# 1.net
KiCad netlist of a schematic drawn in EAGLE
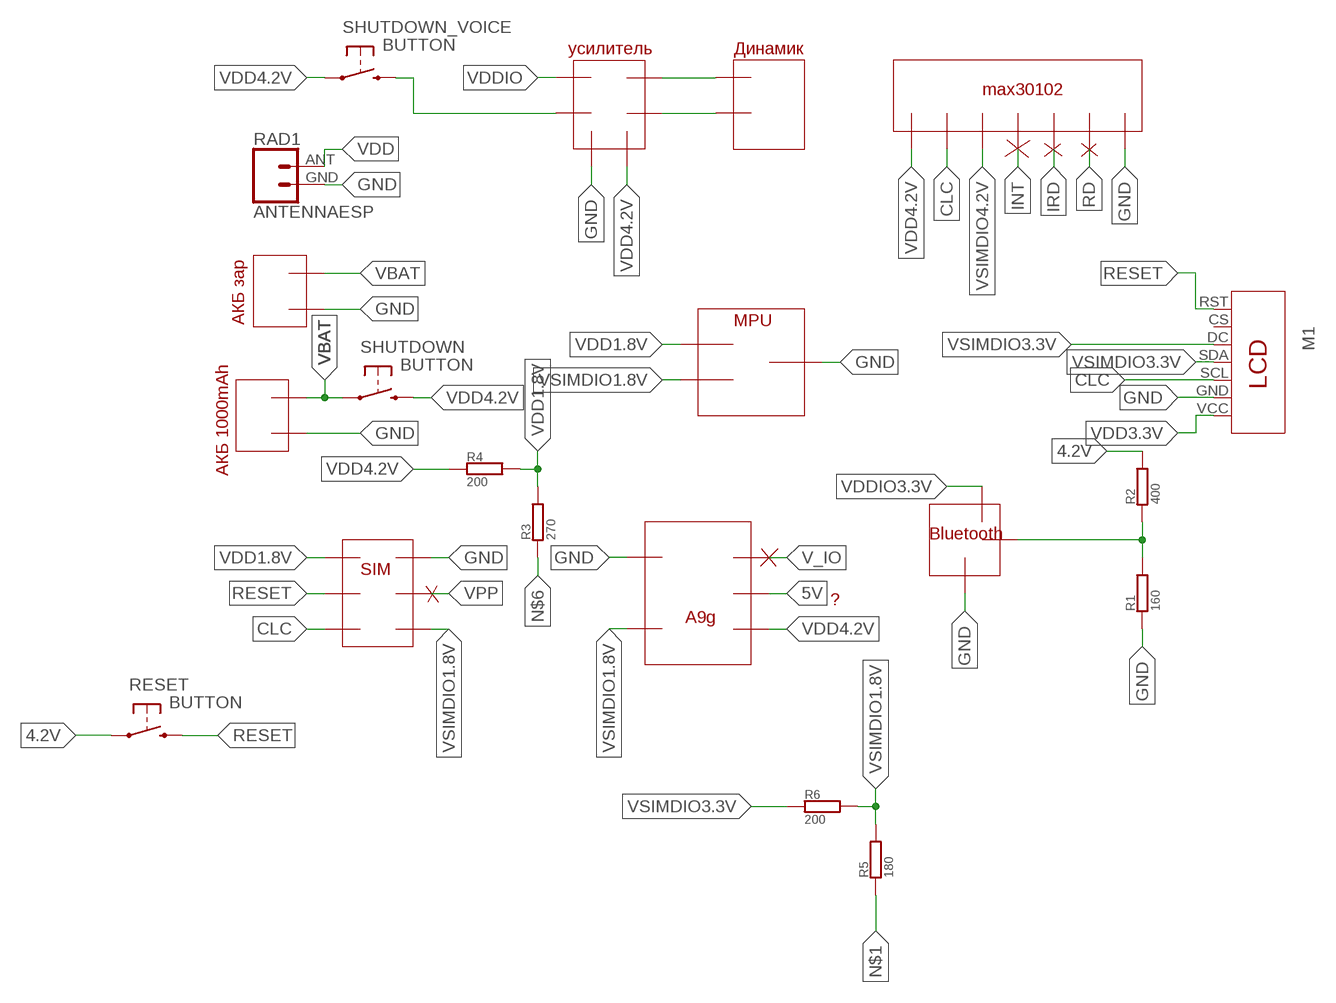
[diagram p0: schematic, sheet 1]

(export (version "E")
  (design (tool "Eeschema 10.0.6"))
  (components
    (comp (ref "M1")
      (value "1.28TFT")
      (footprint "eagle-import:TFT1.28INCH")
      (libsource (lib "eagle-import") (part "1.28TFT"))
    )
    (comp (ref "R1")
      (value "160")
      (footprint "eagle-import:0603")
      (libsource (lib "eagle-import") (part "R0603"))
    )
    (comp (ref "R2")
      (value "400")
      (footprint "eagle-import:0603")
      (libsource (lib "eagle-import") (part "R0603"))
    )
    (comp (ref "R3")
      (value "270")
      (footprint "eagle-import:0603")
      (libsource (lib "eagle-import") (part "R0603"))
    )
    (comp (ref "R4")
      (value "200")
      (footprint "eagle-import:0603")
      (libsource (lib "eagle-import") (part "R0603"))
    )
    (comp (ref "R5")
      (value "180")
      (footprint "eagle-import:0603")
      (libsource (lib "eagle-import") (part "R0603"))
    )
    (comp (ref "R6")
      (value "200")
      (footprint "eagle-import:0603")
      (libsource (lib "eagle-import") (part "R0603"))
    )
    (comp (ref "RAD1")
      (value "ANTENNAESP")
      (footprint "eagle-import:2.4GHZ")
      (libsource (lib "eagle-import") (part "ANTENNAESP"))
    )
    (comp (ref "RESET")
      (value "BUTTON")
      (footprint "eagle-import:BUTTON")
      (libsource (lib "eagle-import") (part "BUTTON"))
    )
    (comp (ref "SHUTDOWN")
      (value "BUTTON")
      (footprint "eagle-import:BUTTON")
      (libsource (lib "eagle-import") (part "BUTTON"))
    )
    (comp (ref "SHUTDOWN_VOICE")
      (value "BUTTON")
      (footprint "eagle-import:BUTTON")
      (libsource (lib "eagle-import") (part "BUTTON"))
    )
  )
  (nets
    (net (code "1") (name "4.2V") (class "Default")
      (node (ref "R2") (pin "P$2") (pinfunction "P$2_P$2") (pintype "bidirectional"))
      (node (ref "RESET") (pin "1") (pinfunction "3_1") (pintype "passive"))
    )
    (net (code "3") (name "CLC") (class "Default")
      (node (ref "M1") (pin "SCL") (pinfunction "P$5_SCL") (pintype "bidirectional"))
    )
    (net (code "4") (name "GND") (class "Default")
      (node (ref "M1") (pin "GND") (pinfunction "P$6_GND") (pintype "bidirectional"))
      (node (ref "R1") (pin "P$1") (pinfunction "P$1_P$1") (pintype "bidirectional"))
      (node (ref "RAD1") (pin "GND") (pinfunction "GND_GND") (pintype "passive"))
    )
    (net (code "7") (name "N$1") (class "Default")
      (node (ref "R5") (pin "P$1") (pinfunction "P$1_P$1") (pintype "bidirectional"))
    )
    (net (code "8") (name "N$6") (class "Default")
      (node (ref "R3") (pin "P$1") (pinfunction "P$1_P$1") (pintype "bidirectional"))
    )
    (net (code "9") (name "Net-(R1-PadP$2)") (class "Default")
      (node (ref "R1") (pin "P$2") (pinfunction "P$2_P$2") (pintype "bidirectional"))
      (node (ref "R2") (pin "P$1") (pinfunction "P$1_P$1") (pintype "bidirectional"))
    )
    (net (code "11") (name "RESET") (class "Default")
      (node (ref "M1") (pin "RST") (pinfunction "P$1_RST") (pintype "bidirectional"))
      (node (ref "RESET") (pin "2") (pinfunction "4_2") (pintype "passive"))
    )
    (net (code "12") (name "VBAT") (class "Default")
      (node (ref "SHUTDOWN") (pin "1") (pinfunction "3_1") (pintype "passive"))
    )
    (net (code "13") (name "VDD") (class "Default")
      (node (ref "RAD1") (pin "ANT") (pinfunction "ANTENNA_ANT") (pintype "passive"))
    )
    (net (code "14") (name "VDD1.8V") (class "Default")
      (node (ref "R3") (pin "P$2") (pinfunction "P$2_P$2") (pintype "bidirectional"))
      (node (ref "R4") (pin "P$2") (pinfunction "P$2_P$2") (pintype "bidirectional"))
    )
    (net (code "15") (name "VDD3.3V") (class "Default")
      (node (ref "M1") (pin "VCC") (pinfunction "P$7_VCC") (pintype "bidirectional"))
    )
    (net (code "16") (name "VDD4.2V") (class "Default")
      (node (ref "R4") (pin "P$1") (pinfunction "P$1_P$1") (pintype "bidirectional"))
      (node (ref "SHUTDOWN") (pin "2") (pinfunction "4_2") (pintype "passive"))
      (node (ref "SHUTDOWN_VOICE") (pin "1") (pinfunction "3_1") (pintype "passive"))
    )
    (net (code "20") (name "VSIMDIO1.8V") (class "Default")
      (node (ref "R5") (pin "P$2") (pinfunction "P$2_P$2") (pintype "bidirectional"))
      (node (ref "R6") (pin "P$2") (pinfunction "P$2_P$2") (pintype "bidirectional"))
    )
    (net (code "21") (name "VSIMDIO3.3V") (class "Default")
      (node (ref "M1") (pin "DC") (pinfunction "P$3_DC") (pintype "bidirectional"))
      (node (ref "M1") (pin "SDA") (pinfunction "P$4_SDA") (pintype "bidirectional"))
      (node (ref "R6") (pin "P$1") (pinfunction "P$1_P$1") (pintype "bidirectional"))
    )
    (net (code "24") (name "unconnected-(M1-P$2-PadCS)") (class "Default")
      (node (ref "M1") (pin "CS") (pinfunction "P$2_CS") (pintype "bidirectional"))
    )
    (net (code "25") (name "unconnected-(SHUTDOWN_VOICE-4-Pad2)") (class "Default")
      (node (ref "SHUTDOWN_VOICE") (pin "2") (pinfunction "4_2") (pintype "passive"))
    )
  )
)
